# STM32SchDoc.net
KiCad netlist of a schematic drawn in Altium Designer
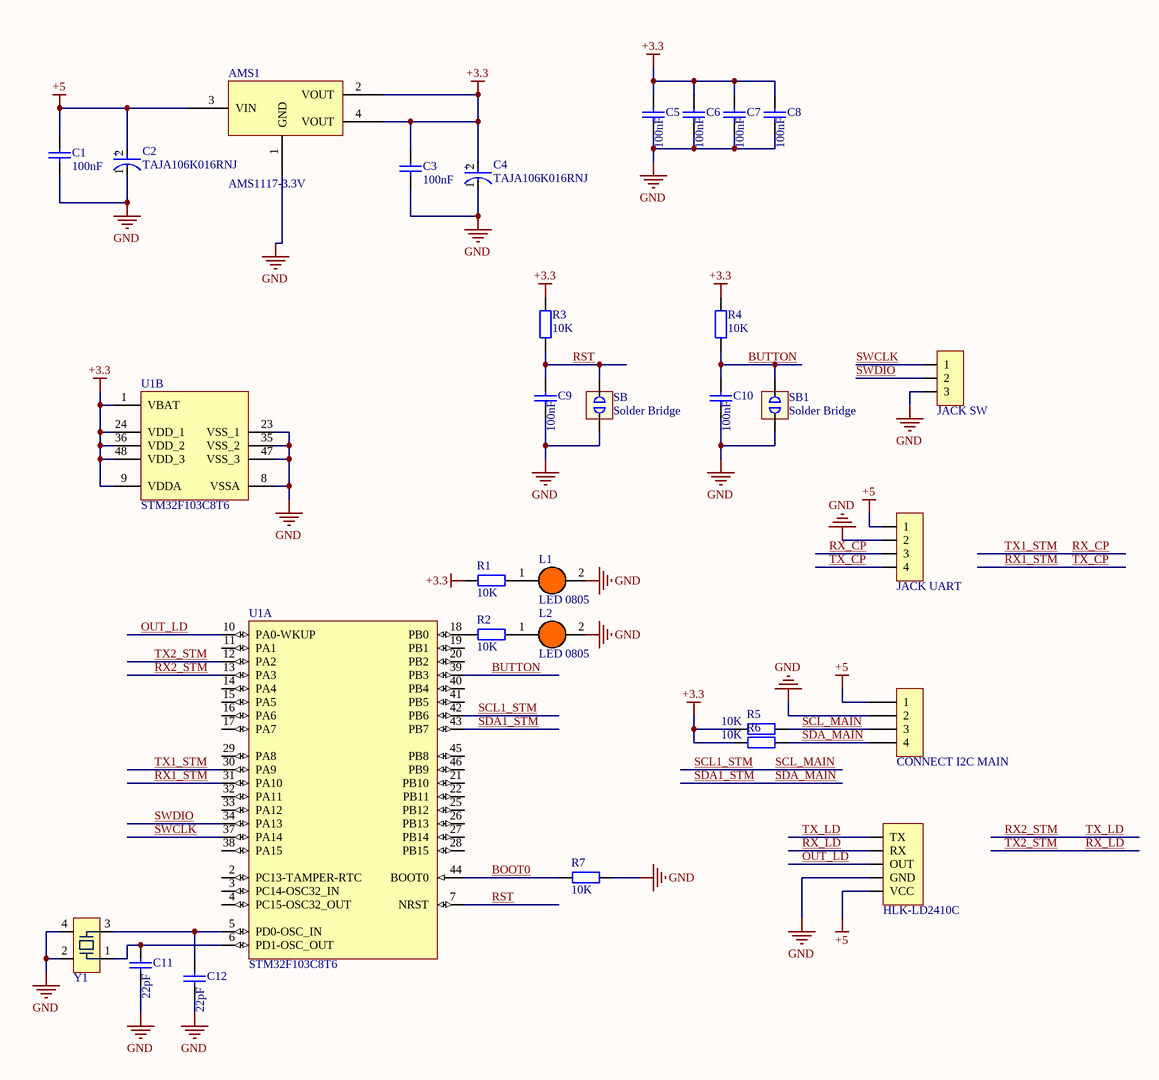
[diagram p0: STM32SchDoc.SchDoc]

(export (version "E")
  (design (tool "Eeschema 10.0.6"))
  (components
    (comp (ref "AMS1")
      (value "AMS1117-3.3V")
      (footprint "SOT223")
      (description "Dán")
      (libsource (lib "Altium_Lib_by_KhueNguyenCreator") (part "AMS1117 SMD"))
    )
    (comp (ref "C1")
      (value "100nF")
      (footprint "tu 0603")
      (description "Dán")
      (libsource (lib "Altium_Lib_by_KhueNguyenCreator") (part "Tu 0603 102 50V 10%"))
    )
    (comp (ref "C2")
      (value "TAJA106K016RNJ")
      (footprint "FP-TAJA-MFG")
      (description "10uF 16V  ±10% 3Ω 1206  SMD Tantalum Capacitor")
      (fields (field (name "VOLTAGE") "16V") (field (name "TOLERANCE") "10%"))
      (libsource (lib "Altium Content Vault") (part "203bc49f2ac43e59fd269a8c329ed05"))
    )
    (comp (ref "C3")
      (value "100nF")
      (footprint "tu 0603")
      (description "Dán")
      (libsource (lib "Altium_Lib_by_KhueNguyenCreator") (part "Tu 0603 102 50V 10%"))
    )
    (comp (ref "C4")
      (value "TAJA106K016RNJ")
      (footprint "FP-TAJA-MFG")
      (description "10uF 16V  ±10% 3Ω 1206  SMD Tantalum Capacitor")
      (fields (field (name "VOLTAGE") "16V") (field (name "TOLERANCE") "10%"))
      (libsource (lib "Altium Content Vault") (part "203bc49f2ac43e59fd269a8c329ed05"))
    )
    (comp (ref "C5")
      (value "100nF")
      (footprint "tu 0603")
      (description "Dán")
      (libsource (lib "Altium_Lib_by_KhueNguyenCreator") (part "Tu 0603 102 50V 10%"))
    )
    (comp (ref "C6")
      (value "100nF")
      (footprint "tu 0603")
      (description "Dán")
      (libsource (lib "Altium_Lib_by_KhueNguyenCreator") (part "Tu 0603 102 50V 10%"))
    )
    (comp (ref "C7")
      (value "100nF")
      (footprint "tu 0603")
      (description "Dán")
      (libsource (lib "Altium_Lib_by_KhueNguyenCreator") (part "Tu 0603 102 50V 10%"))
    )
    (comp (ref "C8")
      (value "100nF")
      (footprint "tu 0603")
      (description "Dán")
      (libsource (lib "Altium_Lib_by_KhueNguyenCreator") (part "Tu 0603 102 50V 10%"))
    )
    (comp (ref "C9")
      (value "100nF")
      (footprint "tu 0603")
      (description "Dán")
      (libsource (lib "Altium_Lib_by_KhueNguyenCreator") (part "Tu 0603 102 50V 10%"))
    )
    (comp (ref "C10")
      (value "100nF")
      (footprint "tu 0603")
      (description "Dán")
      (libsource (lib "Altium_Lib_by_KhueNguyenCreator") (part "Tu 0603 102 50V 10%"))
    )
    (comp (ref "C11")
      (value "22pF")
      (footprint "tu 0603")
      (description "Dán")
      (libsource (lib "Altium_Lib_by_KhueNguyenCreator") (part "Tu 0603 102 50V 10%"))
    )
    (comp (ref "C12")
      (value "22pF")
      (footprint "tu 0603")
      (description "Dán")
      (libsource (lib "Altium_Lib_by_KhueNguyenCreator") (part "Tu 0603 102 50V 10%"))
    )
    (comp (ref "H1")
      (value "CONNECT I2C MAIN")
      (footprint "XH2.54M-4")
      (description "Cắm")
      (libsource (lib "Altium_Lib_by_KhueNguyenCreator") (part "Header 4P 2.54 Duc Thang"))
    )
    (comp (ref "JP1")
      (value "JACK SW")
      (footprint "JP 1x3 DT")
      (description "Cắm")
      (libsource (lib "Altium_Lib_by_KhueNguyenCreator") (part "JP 1x3 2.54 Duc Thang"))
    )
    (comp (ref "JP2")
      (value "JACK UART")
      (footprint "JP 1x4 DT")
      (description "Cắm")
      (libsource (lib "Altium_Lib_by_KhueNguyenCreator") (part "JP 1x4 2.54 Duc Thang"))
    )
    (comp (ref "L1")
      (value "LED 0805")
      (footprint "LED-0805-Orange")
      (description "Dán")
      (libsource (lib "Altium_Lib_by_KhueNguyenCreator") (part "LED 0805 Cam"))
    )
    (comp (ref "L2")
      (value "LED 0805")
      (footprint "LED-0805-Orange")
      (description "Dán")
      (libsource (lib "Altium_Lib_by_KhueNguyenCreator") (part "LED 0805 Cam"))
    )
    (comp (ref "R1")
      (value "10K")
      (footprint "tro smd 0603")
      (description "Dán")
      (libsource (lib "Altium_Lib_by_KhueNguyenCreator") (part "Tro 0603 1% 0R"))
    )
    (comp (ref "R2")
      (value "10K")
      (footprint "tro smd 0603")
      (description "Dán")
      (libsource (lib "Altium_Lib_by_KhueNguyenCreator") (part "Tro 0603 1% 0R"))
    )
    (comp (ref "R3")
      (value "10K")
      (footprint "tro smd 0603")
      (description "Dán")
      (libsource (lib "Altium_Lib_by_KhueNguyenCreator") (part "Tro 0603 1% 0R"))
    )
    (comp (ref "R4")
      (value "10K")
      (footprint "tro smd 0603")
      (description "Dán")
      (libsource (lib "Altium_Lib_by_KhueNguyenCreator") (part "Tro 0603 1% 0R"))
    )
    (comp (ref "R5")
      (value "10K")
      (footprint "tro smd 0603")
      (description "Dán")
      (libsource (lib "Altium_Lib_by_KhueNguyenCreator") (part "Tro 0603 1% 0R"))
    )
    (comp (ref "R6")
      (value "10K")
      (footprint "tro smd 0603")
      (description "Dán")
      (libsource (lib "Altium_Lib_by_KhueNguyenCreator") (part "Tro 0603 1% 0R"))
    )
    (comp (ref "R7")
      (value "10K")
      (footprint "tro smd 0603")
      (description "Dán")
      (libsource (lib "Altium_Lib_by_KhueNguyenCreator") (part "Tro 0603 1% 0R"))
    )
    (comp (ref "SB")
      (value "Solder Bridge")
      (footprint "SB2_NO")
      (description "Solder Bridge 2")
      (libsource (lib "BYTECH_HW_LIB_2019") (part "SB 2 NO"))
    )
    (comp (ref "SB1")
      (value "Solder Bridge")
      (footprint "SB2_NO")
      (description "Solder Bridge 2")
      (libsource (lib "BYTECH_HW_LIB_2019") (part "SB 2 NO"))
    )
    (comp (ref "U1")
      (value "STM32F103C8T6")
      (footprint "48-LQFP")
      (description "IC MCU 32BIT 64KB FLASH 48LQFP")
      (fields (field (name "PART NUMBER") "STMicroelectronics"))
      (libsource (lib "IntegratedLibrary") (part "STM32F103C8T6"))
    )
    (comp (ref "U2")
      (value "HLK-LD2410C")
      (footprint "LD2410C")
      (description "HLK-LD2410C  LD2410C mmWave Sensor")
      (libsource (lib "IntegratedLibrary") (part "HLK-LD2410C"))
    )
    (comp (ref "Y1")
      (value "8MHz")
      (footprint "XTAL_3225")
      (description "XTAL 8MHZ 4 PIN SMD 3225")
      (fields (field (name "MANUFACTURER") "NDK") (field (name "PART NUMBER") "XTAL_4_3225"))
      (libsource (lib "IntegratedLibrary") (part "XTAL_8MHZ_4_PIN"))
    )
  )
  (nets
    (net (code "1") (name "+3.3") (class "Default")
      (node (ref "AMS1") (pin "2") (pinfunction "VOUT_2") (pintype "passive"))
      (node (ref "AMS1") (pin "4") (pinfunction "VOUT_4") (pintype "passive"))
      (node (ref "C3") (pin "1") (pinfunction "1_1") (pintype "passive"))
      (node (ref "C4") (pin "2") (pinfunction "A_2") (pintype "passive"))
      (node (ref "C5") (pin "1") (pinfunction "1_1") (pintype "passive"))
      (node (ref "C6") (pin "1") (pinfunction "1_1") (pintype "passive"))
      (node (ref "C7") (pin "1") (pinfunction "1_1") (pintype "passive"))
      (node (ref "C8") (pin "1") (pinfunction "1_1") (pintype "passive"))
      (node (ref "R1") (pin "1") (pinfunction "1_1") (pintype "passive"))
      (node (ref "R3") (pin "2") (pinfunction "2_2") (pintype "passive"))
      (node (ref "R4") (pin "2") (pinfunction "2_2") (pintype "passive"))
      (node (ref "R5") (pin "1") (pinfunction "1_1") (pintype "passive"))
      (node (ref "R6") (pin "1") (pinfunction "1_1") (pintype "passive"))
      (node (ref "U1") (pin "1") (pinfunction "VBAT_1") (pintype "power_in"))
      (node (ref "U1") (pin "24") (pinfunction "VDD_1_24") (pintype "power_in"))
      (node (ref "U1") (pin "36") (pinfunction "VDD_2_36") (pintype "power_in"))
      (node (ref "U1") (pin "48") (pinfunction "VDD_3_48") (pintype "power_in"))
      (node (ref "U1") (pin "9") (pinfunction "VDDA_9") (pintype "power_in"))
    )
    (net (code "2") (name "+5") (class "Default")
      (node (ref "AMS1") (pin "3") (pinfunction "VIN_3") (pintype "passive"))
      (node (ref "C1") (pin "1") (pinfunction "1_1") (pintype "passive"))
      (node (ref "C2") (pin "2") (pinfunction "A_2") (pintype "passive"))
      (node (ref "H1") (pin "1") (pinfunction "1_1") (pintype "passive"))
      (node (ref "JP2") (pin "1") (pinfunction "1_1") (pintype "passive"))
      (node (ref "U2") (pin "5") (pinfunction "VCC_5") (pintype "passive"))
    )
    (net (code "3") (name "/BOOT0") (class "Default")
      (node (ref "R7") (pin "1") (pinfunction "1_1") (pintype "passive"))
      (node (ref "U1") (pin "44") (pinfunction "BOOT0_44") (pintype "input"))
    )
    (net (code "4") (name "/BUTTON") (class "Default")
      (node (ref "C10") (pin "1") (pinfunction "1_1") (pintype "passive"))
      (node (ref "R4") (pin "1") (pinfunction "1_1") (pintype "passive"))
      (node (ref "SB1") (pin "2") (pinfunction "2_2") (pintype "passive"))
      (node (ref "U1") (pin "39") (pinfunction "PB3_39") (pintype "bidirectional"))
    )
    (net (code "5") (name "/OUT_LD") (class "Default")
      (node (ref "U1") (pin "10") (pinfunction "PA0-WKUP_10") (pintype "bidirectional"))
      (node (ref "U2") (pin "3") (pinfunction "OUT_3") (pintype "passive"))
    )
    (net (code "6") (name "/RST") (class "Default")
      (node (ref "C9") (pin "1") (pinfunction "1_1") (pintype "passive"))
      (node (ref "R3") (pin "1") (pinfunction "1_1") (pintype "passive"))
      (node (ref "SB") (pin "2") (pinfunction "2_2") (pintype "passive"))
      (node (ref "U1") (pin "7") (pinfunction "NRST_7") (pintype "bidirectional"))
    )
    (net (code "7") (name "/RX1_STM") (class "Default")
      (node (ref "JP2") (pin "4") (pinfunction "4_4") (pintype "passive"))
      (node (ref "U1") (pin "31") (pinfunction "PA10_31") (pintype "bidirectional"))
    )
    (net (code "8") (name "/RX2_STM") (class "Default")
      (node (ref "U1") (pin "13") (pinfunction "PA3_13") (pintype "bidirectional"))
      (node (ref "U2") (pin "1") (pinfunction "TX_1") (pintype "passive"))
    )
    (net (code "9") (name "/RX_CP") (class "Default")
      (node (ref "JP2") (pin "3") (pinfunction "3_3") (pintype "passive"))
      (node (ref "U1") (pin "30") (pinfunction "PA9_30") (pintype "bidirectional"))
    )
    (net (code "10") (name "/RX_LD") (class "Default")
      (node (ref "U1") (pin "12") (pinfunction "PA2_12") (pintype "bidirectional"))
      (node (ref "U2") (pin "2") (pinfunction "RX_2") (pintype "passive"))
    )
    (net (code "11") (name "/SCL1_STM") (class "Default")
      (node (ref "H1") (pin "3") (pinfunction "3_3") (pintype "passive"))
      (node (ref "R5") (pin "2") (pinfunction "2_2") (pintype "passive"))
      (node (ref "U1") (pin "42") (pinfunction "PB6_42") (pintype "bidirectional"))
    )
    (net (code "12") (name "/SDA1_STM") (class "Default")
      (node (ref "H1") (pin "4") (pinfunction "4_4") (pintype "passive"))
      (node (ref "R6") (pin "2") (pinfunction "2_2") (pintype "passive"))
      (node (ref "U1") (pin "43") (pinfunction "PB7_43") (pintype "bidirectional"))
    )
    (net (code "13") (name "/SWCLK") (class "Default")
      (node (ref "JP1") (pin "1") (pinfunction "1_1") (pintype "passive"))
      (node (ref "U1") (pin "37") (pinfunction "PA14_37") (pintype "bidirectional"))
    )
    (net (code "14") (name "/SWDIO") (class "Default")
      (node (ref "JP1") (pin "2") (pinfunction "2_2") (pintype "passive"))
      (node (ref "U1") (pin "34") (pinfunction "PA13_34") (pintype "bidirectional"))
    )
    (net (code "15") (name "GND") (class "Default")
      (node (ref "AMS1") (pin "1") (pinfunction "GND_1") (pintype "passive"))
      (node (ref "C1") (pin "2") (pinfunction "2_2") (pintype "passive"))
      (node (ref "C10") (pin "2") (pinfunction "2_2") (pintype "passive"))
      (node (ref "C11") (pin "2") (pinfunction "2_2") (pintype "passive"))
      (node (ref "C12") (pin "2") (pinfunction "2_2") (pintype "passive"))
      (node (ref "C2") (pin "1") (pinfunction "C_1") (pintype "passive"))
      (node (ref "C3") (pin "2") (pinfunction "2_2") (pintype "passive"))
      (node (ref "C4") (pin "1") (pinfunction "C_1") (pintype "passive"))
      (node (ref "C5") (pin "2") (pinfunction "2_2") (pintype "passive"))
      (node (ref "C6") (pin "2") (pinfunction "2_2") (pintype "passive"))
      (node (ref "C7") (pin "2") (pinfunction "2_2") (pintype "passive"))
      (node (ref "C8") (pin "2") (pinfunction "2_2") (pintype "passive"))
      (node (ref "C9") (pin "2") (pinfunction "2_2") (pintype "passive"))
      (node (ref "H1") (pin "2") (pinfunction "2_2") (pintype "passive"))
      (node (ref "JP1") (pin "3") (pinfunction "3_3") (pintype "passive"))
      (node (ref "JP2") (pin "2") (pinfunction "2_2") (pintype "passive"))
      (node (ref "L1") (pin "2") (pinfunction "K_2") (pintype "passive"))
      (node (ref "L2") (pin "2") (pinfunction "K_2") (pintype "passive"))
      (node (ref "R7") (pin "2") (pinfunction "2_2") (pintype "passive"))
      (node (ref "SB") (pin "1") (pinfunction "1_1") (pintype "passive"))
      (node (ref "SB1") (pin "1") (pinfunction "1_1") (pintype "passive"))
      (node (ref "U1") (pin "23") (pinfunction "VSS_1_23") (pintype "power_in"))
      (node (ref "U1") (pin "35") (pinfunction "VSS_2_35") (pintype "power_in"))
      (node (ref "U1") (pin "47") (pinfunction "VSS_3_47") (pintype "power_in"))
      (node (ref "U1") (pin "8") (pinfunction "VSSA_8") (pintype "power_in"))
      (node (ref "U2") (pin "4") (pinfunction "GND_4") (pintype "passive"))
      (node (ref "Y1") (pin "2") (pinfunction "2_2") (pintype "passive"))
      (node (ref "Y1") (pin "4") (pinfunction "4_4") (pintype "passive"))
    )
    (net (code "16") (name "Net-(L1-A)") (class "Default")
      (node (ref "L1") (pin "1") (pinfunction "A_1") (pintype "passive"))
      (node (ref "R1") (pin "2") (pinfunction "2_2") (pintype "passive"))
    )
    (net (code "17") (name "Net-(L2-A)") (class "Default")
      (node (ref "L2") (pin "1") (pinfunction "A_1") (pintype "passive"))
      (node (ref "R2") (pin "2") (pinfunction "2_2") (pintype "passive"))
    )
    (net (code "18") (name "Net-(U1A-PB0)") (class "Default")
      (node (ref "R2") (pin "1") (pinfunction "1_1") (pintype "passive"))
      (node (ref "U1") (pin "18") (pinfunction "PB0_18") (pintype "bidirectional"))
    )
    (net (code "19") (name "Net-(U1A-PD0-OSC_IN)") (class "Default")
      (node (ref "C12") (pin "1") (pinfunction "1_1") (pintype "passive"))
      (node (ref "U1") (pin "5") (pinfunction "PD0-OSC_IN_5") (pintype "bidirectional"))
      (node (ref "Y1") (pin "3") (pinfunction "3_3") (pintype "passive"))
    )
    (net (code "20") (name "Net-(U1A-PD1-OSC_OUT)") (class "Default")
      (node (ref "C11") (pin "1") (pinfunction "1_1") (pintype "passive"))
      (node (ref "U1") (pin "6") (pinfunction "PD1-OSC_OUT_6") (pintype "bidirectional"))
      (node (ref "Y1") (pin "1") (pinfunction "1_1") (pintype "passive"))
    )
    (net (code "21") (name "unconnected-(U1A-PA1-Pad11)") (class "Default")
      (node (ref "U1") (pin "11") (pinfunction "PA1_11") (pintype "bidirectional"))
    )
    (net (code "22") (name "unconnected-(U1A-PA4-Pad14)") (class "Default")
      (node (ref "U1") (pin "14") (pinfunction "PA4_14") (pintype "bidirectional"))
    )
    (net (code "23") (name "unconnected-(U1A-PA5-Pad15)") (class "Default")
      (node (ref "U1") (pin "15") (pinfunction "PA5_15") (pintype "bidirectional"))
    )
    (net (code "24") (name "unconnected-(U1A-PA6-Pad16)") (class "Default")
      (node (ref "U1") (pin "16") (pinfunction "PA6_16") (pintype "bidirectional"))
    )
    (net (code "25") (name "unconnected-(U1A-PA7-Pad17)") (class "Default")
      (node (ref "U1") (pin "17") (pinfunction "PA7_17") (pintype "bidirectional"))
    )
    (net (code "26") (name "unconnected-(U1A-PA8-Pad29)") (class "Default")
      (node (ref "U1") (pin "29") (pinfunction "PA8_29") (pintype "bidirectional"))
    )
    (net (code "27") (name "unconnected-(U1A-PA11-Pad32)") (class "Default")
      (node (ref "U1") (pin "32") (pinfunction "PA11_32") (pintype "bidirectional"))
    )
    (net (code "28") (name "unconnected-(U1A-PA12-Pad33)") (class "Default")
      (node (ref "U1") (pin "33") (pinfunction "PA12_33") (pintype "bidirectional"))
    )
    (net (code "29") (name "unconnected-(U1A-PA15-Pad38)") (class "Default")
      (node (ref "U1") (pin "38") (pinfunction "PA15_38") (pintype "bidirectional"))
    )
    (net (code "30") (name "unconnected-(U1A-PB1-Pad19)") (class "Default")
      (node (ref "U1") (pin "19") (pinfunction "PB1_19") (pintype "bidirectional"))
    )
    (net (code "31") (name "unconnected-(U1A-PB2-Pad20)") (class "Default")
      (node (ref "U1") (pin "20") (pinfunction "PB2_20") (pintype "bidirectional"))
    )
    (net (code "32") (name "unconnected-(U1A-PB4-Pad40)") (class "Default")
      (node (ref "U1") (pin "40") (pinfunction "PB4_40") (pintype "bidirectional"))
    )
    (net (code "33") (name "unconnected-(U1A-PB5-Pad41)") (class "Default")
      (node (ref "U1") (pin "41") (pinfunction "PB5_41") (pintype "bidirectional"))
    )
    (net (code "34") (name "unconnected-(U1A-PB8-Pad45)") (class "Default")
      (node (ref "U1") (pin "45") (pinfunction "PB8_45") (pintype "bidirectional"))
    )
    (net (code "35") (name "unconnected-(U1A-PB9-Pad46)") (class "Default")
      (node (ref "U1") (pin "46") (pinfunction "PB9_46") (pintype "bidirectional"))
    )
    (net (code "36") (name "unconnected-(U1A-PB10-Pad21)") (class "Default")
      (node (ref "U1") (pin "21") (pinfunction "PB10_21") (pintype "bidirectional"))
    )
    (net (code "37") (name "unconnected-(U1A-PB11-Pad22)") (class "Default")
      (node (ref "U1") (pin "22") (pinfunction "PB11_22") (pintype "bidirectional"))
    )
    (net (code "38") (name "unconnected-(U1A-PB12-Pad25)") (class "Default")
      (node (ref "U1") (pin "25") (pinfunction "PB12_25") (pintype "bidirectional"))
    )
    (net (code "39") (name "unconnected-(U1A-PB13-Pad26)") (class "Default")
      (node (ref "U1") (pin "26") (pinfunction "PB13_26") (pintype "bidirectional"))
    )
    (net (code "40") (name "unconnected-(U1A-PB14-Pad27)") (class "Default")
      (node (ref "U1") (pin "27") (pinfunction "PB14_27") (pintype "bidirectional"))
    )
    (net (code "41") (name "unconnected-(U1A-PB15-Pad28)") (class "Default")
      (node (ref "U1") (pin "28") (pinfunction "PB15_28") (pintype "bidirectional"))
    )
    (net (code "42") (name "unconnected-(U1A-PC13-TAMPER-RTC-Pad2)") (class "Default")
      (node (ref "U1") (pin "2") (pinfunction "PC13-TAMPER-RTC_2") (pintype "bidirectional"))
    )
    (net (code "43") (name "unconnected-(U1A-PC14-OSC32_IN-Pad3)") (class "Default")
      (node (ref "U1") (pin "3") (pinfunction "PC14-OSC32_IN_3") (pintype "bidirectional"))
    )
    (net (code "44") (name "unconnected-(U1A-PC15-OSC32_OUT-Pad4)") (class "Default")
      (node (ref "U1") (pin "4") (pinfunction "PC15-OSC32_OUT_4") (pintype "bidirectional"))
    )
  )
)
